# m328p_rfm69_node.net
KiCad netlist of a schematic drawn in EAGLE
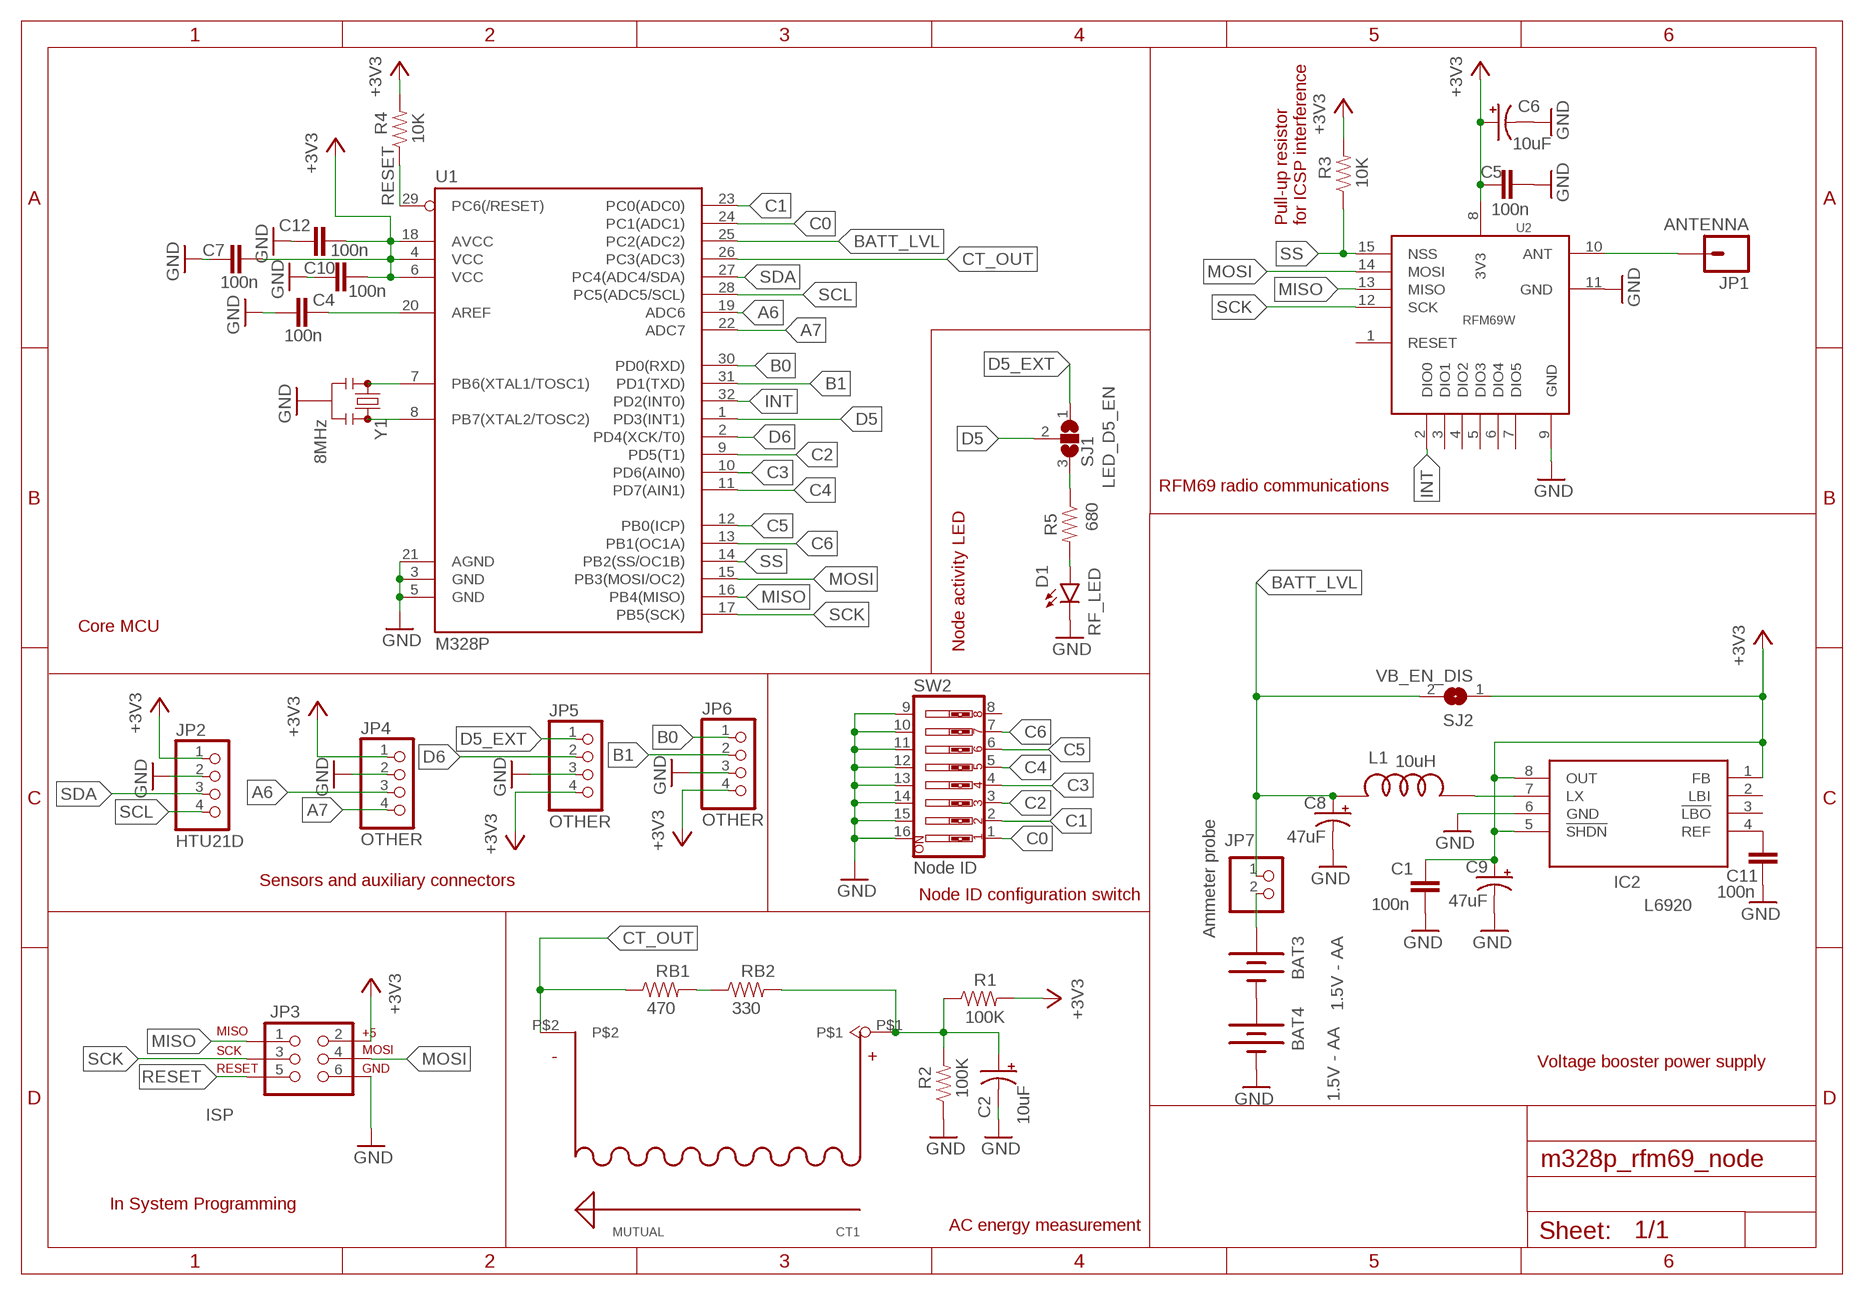
[diagram p0: schematic, sheet 1]

(export (version "E")
  (design (tool "Eeschema 10.0.6"))
  (components
    (comp (ref "BAT3")
      (value "1.5V - AA")
      (footprint "eagle-import:BATTERY-AA-KIT")
      (libsource (lib "eagle-import") (part "BATTERYAA-KIT"))
    )
    (comp (ref "BAT4")
      (value "1.5V - AA")
      (footprint "eagle-import:BATTERY-AA-KIT")
      (libsource (lib "eagle-import") (part "BATTERYAA-KIT"))
    )
    (comp (ref "C1")
      (value "100n")
      (footprint "eagle-import:0805")
      (libsource (lib "eagle-import") (part "CAP0805"))
    )
    (comp (ref "C2")
      (value "10uF")
      (footprint "eagle-import:EIA3528")
      (libsource (lib "eagle-import") (part "47UF-TANT"))
    )
    (comp (ref "C4")
      (value "100n")
      (footprint "eagle-import:0805")
      (libsource (lib "eagle-import") (part "CAP0805"))
    )
    (comp (ref "C5")
      (value "100n")
      (footprint "eagle-import:0805")
      (libsource (lib "eagle-import") (part "CAP0805"))
    )
    (comp (ref "C6")
      (value "10uF")
      (footprint "eagle-import:EIA3528")
      (libsource (lib "eagle-import") (part "47UF-TANT"))
    )
    (comp (ref "C7")
      (value "100n")
      (footprint "eagle-import:0805")
      (libsource (lib "eagle-import") (part "CAP0805"))
    )
    (comp (ref "C8")
      (value "47uF")
      (footprint "eagle-import:EIA3528")
      (libsource (lib "eagle-import") (part "47UF-TANT"))
    )
    (comp (ref "C9")
      (value "47uF")
      (footprint "eagle-import:EIA3528")
      (libsource (lib "eagle-import") (part "47UF-TANT"))
    )
    (comp (ref "C10")
      (value "100n")
      (footprint "eagle-import:0805")
      (libsource (lib "eagle-import") (part "CAP0805"))
    )
    (comp (ref "C11")
      (value "100n")
      (footprint "eagle-import:0805")
      (libsource (lib "eagle-import") (part "CAP0805"))
    )
    (comp (ref "C12")
      (value "100n")
      (footprint "eagle-import:0805")
      (libsource (lib "eagle-import") (part "CAP0805"))
    )
    (comp (ref "CT1")
      (value "MUTUAL")
      (footprint "eagle-import:MUTUAL")
      (libsource (lib "eagle-import") (part "MUTUAL"))
    )
    (comp (ref "D1")
      (value "RF_LED")
      (footprint "eagle-import:LED-0603")
      (libsource (lib "eagle-import") (part "LED0603"))
    )
    (comp (ref "IC2")
      (value "L6920")
      (footprint "eagle-import:TSSOP8")
      (libsource (lib "eagle-import") (part "L6920TSSOP8"))
    )
    (comp (ref "JP1")
      (value "ANTENNA")
      (footprint "eagle-import:LUXEON-PAD")
      (libsource (lib "eagle-import") (part "M01SMD"))
    )
    (comp (ref "JP2")
      (value "HTU21D")
      (footprint "eagle-import:1X04")
      (libsource (lib "eagle-import") (part "PINHD-1X4"))
    )
    (comp (ref "JP3")
      (value "ISP")
      (footprint "eagle-import:2X3-NS")
      (libsource (lib "eagle-import") (part "AVR_SPI_PRG_6NS"))
    )
    (comp (ref "JP4")
      (value "OTHER")
      (footprint "eagle-import:1X04")
      (libsource (lib "eagle-import") (part "PINHD-1X4"))
    )
    (comp (ref "JP5")
      (value "OTHER")
      (footprint "eagle-import:1X04")
      (libsource (lib "eagle-import") (part "PINHD-1X4"))
    )
    (comp (ref "JP6")
      (value "OTHER")
      (footprint "eagle-import:1X04")
      (libsource (lib "eagle-import") (part "PINHD-1X4"))
    )
    (comp (ref "JP7")
      (value "Ammeter probe")
      (footprint "eagle-import:1X02")
      (libsource (lib "eagle-import") (part "PINHD-1X2"))
    )
    (comp (ref "L1")
      (value "10uH")
      (footprint "eagle-import:DLJ-4018")
      (libsource (lib "eagle-import") (part "DLJ-4018"))
    )
    (comp (ref "R1")
      (value "100K")
      (footprint "eagle-import:0805")
      (libsource (lib "eagle-import") (part "SparkFun-Resistors_RESISTOR0805-RES"))
    )
    (comp (ref "R2")
      (value "100K")
      (footprint "eagle-import:0805")
      (libsource (lib "eagle-import") (part "SparkFun-Resistors_RESISTOR0805-RES"))
    )
    (comp (ref "R3")
      (value "10K")
      (footprint "eagle-import:0805")
      (libsource (lib "eagle-import") (part "SparkFun-Resistors_RESISTOR0805-RES"))
    )
    (comp (ref "R4")
      (value "10K")
      (footprint "eagle-import:0805")
      (libsource (lib "eagle-import") (part "SparkFun-Resistors_RESISTOR0805-RES"))
    )
    (comp (ref "R5")
      (value "680")
      (footprint "eagle-import:0805")
      (libsource (lib "eagle-import") (part "RESISTOR0805-RES"))
    )
    (comp (ref "RB1")
      (value "470")
      (footprint "eagle-import:0805")
      (libsource (lib "eagle-import") (part "SparkFun-Resistors_RESISTOR0805-RES"))
    )
    (comp (ref "RB2")
      (value "330")
      (footprint "eagle-import:0805")
      (libsource (lib "eagle-import") (part "SparkFun-Resistors_RESISTOR0805-RES"))
    )
    (comp (ref "SJ1")
      (value "LED_D5_EN")
      (footprint "eagle-import:SJ_2")
      (libsource (lib "eagle-import") (part "SJ2W"))
    )
    (comp (ref "SJ2")
      (value "VB_EN_DIS")
      (footprint "eagle-import:SJ")
      (libsource (lib "eagle-import") (part "SJ"))
    )
    (comp (ref "SW2")
      (value "Node ID")
      (footprint "eagle-import:DIPSWITCH-08-50MIL")
      (libsource (lib "eagle-import") (part "SW_DIP-8-SMT-HALFSIZE"))
    )
    (comp (ref "U1")
      (value "M328P")
      (footprint "eagle-import:TQFP32-08")
      (libsource (lib "eagle-import") (part "ATMEGA328P_TQFP"))
    )
    (comp (ref "U2")
      (value "RFM69W")
      (footprint "eagle-import:RFM69W")
      (libsource (lib "eagle-import") (part "RFM69W"))
    )
    (comp (ref "Y1")
      (value "8MHz")
      (footprint "eagle-import:RESONATOR-SMD_MED")
      (libsource (lib "eagle-import") (part "RESONATOR4MHZ"))
    )
  )
  (nets
    (net (code "1") (name "+3V3") (class "Default")
      (node (ref "C1") (pin "1") (pinfunction "1_1") (pintype "passive"))
      (node (ref "C10") (pin "2") (pinfunction "2_2") (pintype "passive"))
      (node (ref "C12") (pin "2") (pinfunction "2_2") (pintype "passive"))
      (node (ref "C5") (pin "1") (pinfunction "1_1") (pintype "passive"))
      (node (ref "C6") (pin "A") (pinfunction "+_A") (pintype "passive"))
      (node (ref "C7") (pin "2") (pinfunction "2_2") (pintype "passive"))
      (node (ref "C9") (pin "A") (pinfunction "+_A") (pintype "passive"))
      (node (ref "IC2") (pin "1") (pinfunction "FB_1") (pintype "bidirectional"))
      (node (ref "IC2") (pin "5") (pinfunction "~{SHDN}_5") (pintype "bidirectional"))
      (node (ref "IC2") (pin "8") (pinfunction "OUT_8") (pintype "bidirectional"))
      (node (ref "JP2") (pin "1") (pinfunction "1_1") (pintype "passive"))
      (node (ref "JP3") (pin "2") (pinfunction "2_2") (pintype "passive"))
      (node (ref "JP4") (pin "1") (pinfunction "1_1") (pintype "passive"))
      (node (ref "JP5") (pin "4") (pinfunction "4_4") (pintype "passive"))
      (node (ref "JP6") (pin "4") (pinfunction "4_4") (pintype "passive"))
      (node (ref "R1") (pin "2") (pinfunction "2_2") (pintype "passive"))
      (node (ref "R3") (pin "2") (pinfunction "2_2") (pintype "passive"))
      (node (ref "R4") (pin "2") (pinfunction "2_2") (pintype "passive"))
      (node (ref "SJ2") (pin "1") (pinfunction "1_1") (pintype "passive"))
      (node (ref "U1") (pin "18") (pinfunction "AVCC_18") (pintype "bidirectional"))
      (node (ref "U1") (pin "4") (pinfunction "VCC_4") (pintype "bidirectional"))
      (node (ref "U1") (pin "6") (pinfunction "VCC_6") (pintype "bidirectional"))
      (node (ref "U2") (pin "8") (pinfunction "3V3_8") (pintype "bidirectional"))
    )
    (net (code "2") (name "A6") (class "Default")
      (node (ref "JP4") (pin "3") (pinfunction "3_3") (pintype "passive"))
      (node (ref "U1") (pin "19") (pinfunction "ADC6_19") (pintype "bidirectional"))
    )
    (net (code "3") (name "A7") (class "Default")
      (node (ref "JP4") (pin "4") (pinfunction "4_4") (pintype "passive"))
      (node (ref "U1") (pin "22") (pinfunction "ADC7_22") (pintype "bidirectional"))
    )
    (net (code "4") (name "B0") (class "Default")
      (node (ref "JP6") (pin "1") (pinfunction "1_1") (pintype "passive"))
      (node (ref "U1") (pin "30") (pinfunction "PD0(RXD)_30") (pintype "bidirectional"))
    )
    (net (code "5") (name "B1") (class "Default")
      (node (ref "JP6") (pin "2") (pinfunction "2_2") (pintype "passive"))
      (node (ref "U1") (pin "31") (pinfunction "PD1(TXD)_31") (pintype "bidirectional"))
    )
    (net (code "6") (name "BATT_LVL") (class "Default")
      (node (ref "C8") (pin "A") (pinfunction "+_A") (pintype "passive"))
      (node (ref "JP7") (pin "1") (pinfunction "1_1") (pintype "passive"))
      (node (ref "L1") (pin "P$2") (pinfunction "2_P$2") (pintype "bidirectional"))
      (node (ref "SJ2") (pin "2") (pinfunction "2_2") (pintype "passive"))
      (node (ref "U1") (pin "25") (pinfunction "PC2(ADC2)_25") (pintype "bidirectional"))
    )
    (net (code "7") (name "C0") (class "Default")
      (node (ref "SW2") (pin "1") (pinfunction "1_1") (pintype "passive"))
      (node (ref "U1") (pin "24") (pinfunction "PC1(ADC1)_24") (pintype "bidirectional"))
    )
    (net (code "8") (name "C1") (class "Default")
      (node (ref "SW2") (pin "2") (pinfunction "2_2") (pintype "passive"))
      (node (ref "U1") (pin "23") (pinfunction "PC0(ADC0)_23") (pintype "bidirectional"))
    )
    (net (code "9") (name "C2") (class "Default")
      (node (ref "SW2") (pin "3") (pinfunction "3_3") (pintype "passive"))
      (node (ref "U1") (pin "9") (pinfunction "PD5(T1)_9") (pintype "bidirectional"))
    )
    (net (code "10") (name "C3") (class "Default")
      (node (ref "SW2") (pin "4") (pinfunction "4_4") (pintype "passive"))
      (node (ref "U1") (pin "10") (pinfunction "PD6(AIN0)_10") (pintype "bidirectional"))
    )
    (net (code "11") (name "C4") (class "Default")
      (node (ref "SW2") (pin "5") (pinfunction "5_5") (pintype "passive"))
      (node (ref "U1") (pin "11") (pinfunction "PD7(AIN1)_11") (pintype "bidirectional"))
    )
    (net (code "12") (name "C5") (class "Default")
      (node (ref "SW2") (pin "6") (pinfunction "6_6") (pintype "passive"))
      (node (ref "U1") (pin "12") (pinfunction "PB0(ICP)_12") (pintype "bidirectional"))
    )
    (net (code "13") (name "C6") (class "Default")
      (node (ref "SW2") (pin "7") (pinfunction "7_7") (pintype "passive"))
      (node (ref "U1") (pin "13") (pinfunction "PB1(OC1A)_13") (pintype "bidirectional"))
    )
    (net (code "14") (name "CT_OUT") (class "Default")
      (node (ref "CT1") (pin "P$2") (pinfunction "P$2_P$2") (pintype "bidirectional"))
      (node (ref "RB1") (pin "1") (pinfunction "1_1") (pintype "passive"))
      (node (ref "U1") (pin "26") (pinfunction "PC3(ADC3)_26") (pintype "bidirectional"))
    )
    (net (code "15") (name "D5") (class "Default")
      (node (ref "SJ1") (pin "2") (pinfunction "2_2") (pintype "passive"))
      (node (ref "U1") (pin "1") (pinfunction "PD3(INT1)_1") (pintype "bidirectional"))
    )
    (net (code "16") (name "D5_EXT") (class "Default")
      (node (ref "JP5") (pin "1") (pinfunction "1_1") (pintype "passive"))
      (node (ref "SJ1") (pin "1") (pinfunction "1_1") (pintype "passive"))
    )
    (net (code "17") (name "D6") (class "Default")
      (node (ref "JP5") (pin "2") (pinfunction "2_2") (pintype "passive"))
      (node (ref "U1") (pin "2") (pinfunction "PD4(XCK/T0)_2") (pintype "bidirectional"))
    )
    (net (code "18") (name "GND") (class "Default")
      (node (ref "BAT4") (pin "GND@1") (pinfunction "-_GND@1") (pintype "power_in"))
      (node (ref "C1") (pin "2") (pinfunction "2_2") (pintype "passive"))
      (node (ref "C10") (pin "1") (pinfunction "1_1") (pintype "passive"))
      (node (ref "C11") (pin "2") (pinfunction "2_2") (pintype "passive"))
      (node (ref "C12") (pin "1") (pinfunction "1_1") (pintype "passive"))
      (node (ref "C2") (pin "C") (pinfunction "-_C") (pintype "passive"))
      (node (ref "C4") (pin "1") (pinfunction "1_1") (pintype "passive"))
      (node (ref "C5") (pin "2") (pinfunction "2_2") (pintype "passive"))
      (node (ref "C6") (pin "C") (pinfunction "-_C") (pintype "passive"))
      (node (ref "C7") (pin "1") (pinfunction "1_1") (pintype "passive"))
      (node (ref "C8") (pin "C") (pinfunction "-_C") (pintype "passive"))
      (node (ref "C9") (pin "C") (pinfunction "-_C") (pintype "passive"))
      (node (ref "D1") (pin "C") (pinfunction "C_C") (pintype "passive"))
      (node (ref "IC2") (pin "6") (pinfunction "GND_6") (pintype "bidirectional"))
      (node (ref "JP2") (pin "2") (pinfunction "2_2") (pintype "passive"))
      (node (ref "JP3") (pin "6") (pinfunction "6_6") (pintype "passive"))
      (node (ref "JP4") (pin "2") (pinfunction "2_2") (pintype "passive"))
      (node (ref "JP5") (pin "3") (pinfunction "3_3") (pintype "passive"))
      (node (ref "JP6") (pin "3") (pinfunction "3_3") (pintype "passive"))
      (node (ref "R2") (pin "1") (pinfunction "1_1") (pintype "passive"))
      (node (ref "SW2") (pin "10") (pinfunction "10_10") (pintype "passive"))
      (node (ref "SW2") (pin "11") (pinfunction "11_11") (pintype "passive"))
      (node (ref "SW2") (pin "12") (pinfunction "12_12") (pintype "passive"))
      (node (ref "SW2") (pin "13") (pinfunction "13_13") (pintype "passive"))
      (node (ref "SW2") (pin "14") (pinfunction "14_14") (pintype "passive"))
      (node (ref "SW2") (pin "15") (pinfunction "15_15") (pintype "passive"))
      (node (ref "SW2") (pin "16") (pinfunction "16_16") (pintype "passive"))
      (node (ref "SW2") (pin "9") (pinfunction "9_9") (pintype "passive"))
      (node (ref "U1") (pin "21") (pinfunction "AGND_21") (pintype "bidirectional"))
      (node (ref "U1") (pin "3") (pinfunction "GND_3") (pintype "bidirectional"))
      (node (ref "U1") (pin "5") (pinfunction "GND_5") (pintype "bidirectional"))
      (node (ref "U2") (pin "11") (pinfunction "GND_11") (pintype "bidirectional"))
      (node (ref "U2") (pin "9") (pinfunction "GND_9") (pintype "bidirectional"))
      (node (ref "Y1") (pin "2") (pinfunction "2_2") (pintype "passive"))
    )
    (net (code "19") (name "INT") (class "Default")
      (node (ref "U1") (pin "32") (pinfunction "PD2(INT0)_32") (pintype "bidirectional"))
      (node (ref "U2") (pin "2") (pinfunction "DIO0_2") (pintype "bidirectional"))
    )
    (net (code "20") (name "MISO") (class "Default")
      (node (ref "JP3") (pin "1") (pinfunction "1_1") (pintype "passive"))
      (node (ref "U1") (pin "16") (pinfunction "PB4(MISO)_16") (pintype "bidirectional"))
      (node (ref "U2") (pin "13") (pinfunction "MISO_13") (pintype "bidirectional"))
    )
    (net (code "21") (name "MOSI") (class "Default")
      (node (ref "JP3") (pin "4") (pinfunction "4_4") (pintype "passive"))
      (node (ref "U1") (pin "15") (pinfunction "PB3(MOSI/OC2)_15") (pintype "bidirectional"))
      (node (ref "U2") (pin "14") (pinfunction "MOSI_14") (pintype "bidirectional"))
    )
    (net (code "22") (name "Net-(BAT3-+)") (class "Default")
      (node (ref "BAT3") (pin "PWR@1") (pinfunction "+_PWR@1") (pintype "power_in"))
      (node (ref "JP7") (pin "2") (pinfunction "2_2") (pintype "passive"))
    )
    (net (code "23") (name "Net-(BAT3--)") (class "Default")
      (node (ref "BAT3") (pin "GND@1") (pinfunction "-_GND@1") (pintype "power_in"))
      (node (ref "BAT4") (pin "PWR@1") (pinfunction "+_PWR@1") (pintype "power_in"))
    )
    (net (code "24") (name "Net-(C2-+)") (class "Default")
      (node (ref "C2") (pin "A") (pinfunction "+_A") (pintype "passive"))
      (node (ref "CT1") (pin "P$1") (pinfunction "P$1_P$1") (pintype "bidirectional"))
      (node (ref "R1") (pin "1") (pinfunction "1_1") (pintype "passive"))
      (node (ref "R2") (pin "2") (pinfunction "2_2") (pintype "passive"))
      (node (ref "RB2") (pin "2") (pinfunction "2_2") (pintype "passive"))
    )
    (net (code "25") (name "Net-(D1-PadA)") (class "Default")
      (node (ref "D1") (pin "A") (pinfunction "A_A") (pintype "passive"))
      (node (ref "R5") (pin "2") (pinfunction "2_2") (pintype "passive"))
    )
    (net (code "26") (name "Net-(IC2-LX)") (class "Default")
      (node (ref "IC2") (pin "7") (pinfunction "LX_7") (pintype "bidirectional"))
      (node (ref "L1") (pin "P$1") (pinfunction "1_P$1") (pintype "bidirectional"))
    )
    (net (code "27") (name "Net-(IC2-REF)") (class "Default")
      (node (ref "C11") (pin "1") (pinfunction "1_1") (pintype "passive"))
      (node (ref "IC2") (pin "4") (pinfunction "REF_4") (pintype "bidirectional"))
    )
    (net (code "28") (name "Net-(JP1-1)") (class "Default")
      (node (ref "JP1") (pin "P$1") (pinfunction "1_P$1") (pintype "passive"))
      (node (ref "U2") (pin "10") (pinfunction "ANT_10") (pintype "bidirectional"))
    )
    (net (code "29") (name "Net-(R5-Pad1)") (class "Default")
      (node (ref "R5") (pin "1") (pinfunction "1_1") (pintype "passive"))
      (node (ref "SJ1") (pin "3") (pinfunction "3_3") (pintype "passive"))
    )
    (net (code "30") (name "Net-(RB1-Pad2)") (class "Default")
      (node (ref "RB1") (pin "2") (pinfunction "2_2") (pintype "passive"))
      (node (ref "RB2") (pin "1") (pinfunction "1_1") (pintype "passive"))
    )
    (net (code "31") (name "Net-(U1-AREF)") (class "Default")
      (node (ref "C4") (pin "2") (pinfunction "2_2") (pintype "passive"))
      (node (ref "U1") (pin "20") (pinfunction "AREF_20") (pintype "bidirectional"))
    )
    (net (code "32") (name "Net-(U1-PB6(XTAL1{slash}TOSC1))") (class "Default")
      (node (ref "U1") (pin "7") (pinfunction "PB6(XTAL1/TOSC1)_7") (pintype "bidirectional"))
      (node (ref "Y1") (pin "1") (pinfunction "1_1") (pintype "passive"))
    )
    (net (code "33") (name "Net-(U1-PB7(XTAL2{slash}TOSC2))") (class "Default")
      (node (ref "U1") (pin "8") (pinfunction "PB7(XTAL2/TOSC2)_8") (pintype "bidirectional"))
      (node (ref "Y1") (pin "3") (pinfunction "3_3") (pintype "passive"))
    )
    (net (code "34") (name "RESET") (class "Default")
      (node (ref "JP3") (pin "5") (pinfunction "5_5") (pintype "passive"))
      (node (ref "R4") (pin "1") (pinfunction "1_1") (pintype "passive"))
      (node (ref "U1") (pin "29") (pinfunction "PC6(/RESET)_29") (pintype "bidirectional"))
    )
    (net (code "35") (name "SCK") (class "Default")
      (node (ref "JP3") (pin "3") (pinfunction "3_3") (pintype "passive"))
      (node (ref "U1") (pin "17") (pinfunction "PB5(SCK)_17") (pintype "bidirectional"))
      (node (ref "U2") (pin "12") (pinfunction "SCK_12") (pintype "bidirectional"))
    )
    (net (code "36") (name "SCL") (class "Default")
      (node (ref "JP2") (pin "4") (pinfunction "4_4") (pintype "passive"))
      (node (ref "U1") (pin "28") (pinfunction "PC5(ADC5/SCL)_28") (pintype "bidirectional"))
    )
    (net (code "37") (name "SDA") (class "Default")
      (node (ref "JP2") (pin "3") (pinfunction "3_3") (pintype "passive"))
      (node (ref "U1") (pin "27") (pinfunction "PC4(ADC4/SDA)_27") (pintype "bidirectional"))
    )
    (net (code "38") (name "SS") (class "Default")
      (node (ref "R3") (pin "1") (pinfunction "1_1") (pintype "passive"))
      (node (ref "U1") (pin "14") (pinfunction "PB2(SS/OC1B)_14") (pintype "bidirectional"))
      (node (ref "U2") (pin "15") (pinfunction "NSS_15") (pintype "bidirectional"))
    )
    (net (code "39") (name "unconnected-(IC2-LBI-Pad2)") (class "Default")
      (node (ref "IC2") (pin "2") (pinfunction "LBI_2") (pintype "bidirectional"))
    )
    (net (code "40") (name "unconnected-(IC2-~{LBO}-Pad3)") (class "Default")
      (node (ref "IC2") (pin "3") (pinfunction "~{LBO}_3") (pintype "bidirectional"))
    )
    (net (code "41") (name "unconnected-(SW2-Pad8)") (class "Default")
      (node (ref "SW2") (pin "8") (pinfunction "8_8") (pintype "passive"))
    )
    (net (code "42") (name "unconnected-(U2-DIO1-Pad3)") (class "Default")
      (node (ref "U2") (pin "3") (pinfunction "DIO1_3") (pintype "bidirectional"))
    )
    (net (code "43") (name "unconnected-(U2-DIO2-Pad4)") (class "Default")
      (node (ref "U2") (pin "4") (pinfunction "DIO2_4") (pintype "bidirectional"))
    )
    (net (code "44") (name "unconnected-(U2-DIO3-Pad5)") (class "Default")
      (node (ref "U2") (pin "5") (pinfunction "DIO3_5") (pintype "bidirectional"))
    )
    (net (code "45") (name "unconnected-(U2-DIO4-Pad6)") (class "Default")
      (node (ref "U2") (pin "6") (pinfunction "DIO4_6") (pintype "bidirectional"))
    )
    (net (code "46") (name "unconnected-(U2-DIO5-Pad7)") (class "Default")
      (node (ref "U2") (pin "7") (pinfunction "DIO5_7") (pintype "bidirectional"))
    )
    (net (code "47") (name "unconnected-(U2-RESET-Pad1)") (class "Default")
      (node (ref "U2") (pin "1") (pinfunction "RESET_1") (pintype "bidirectional"))
    )
  )
)
